# cpu.net
KiCad netlist of a schematic drawn in Altium Designer
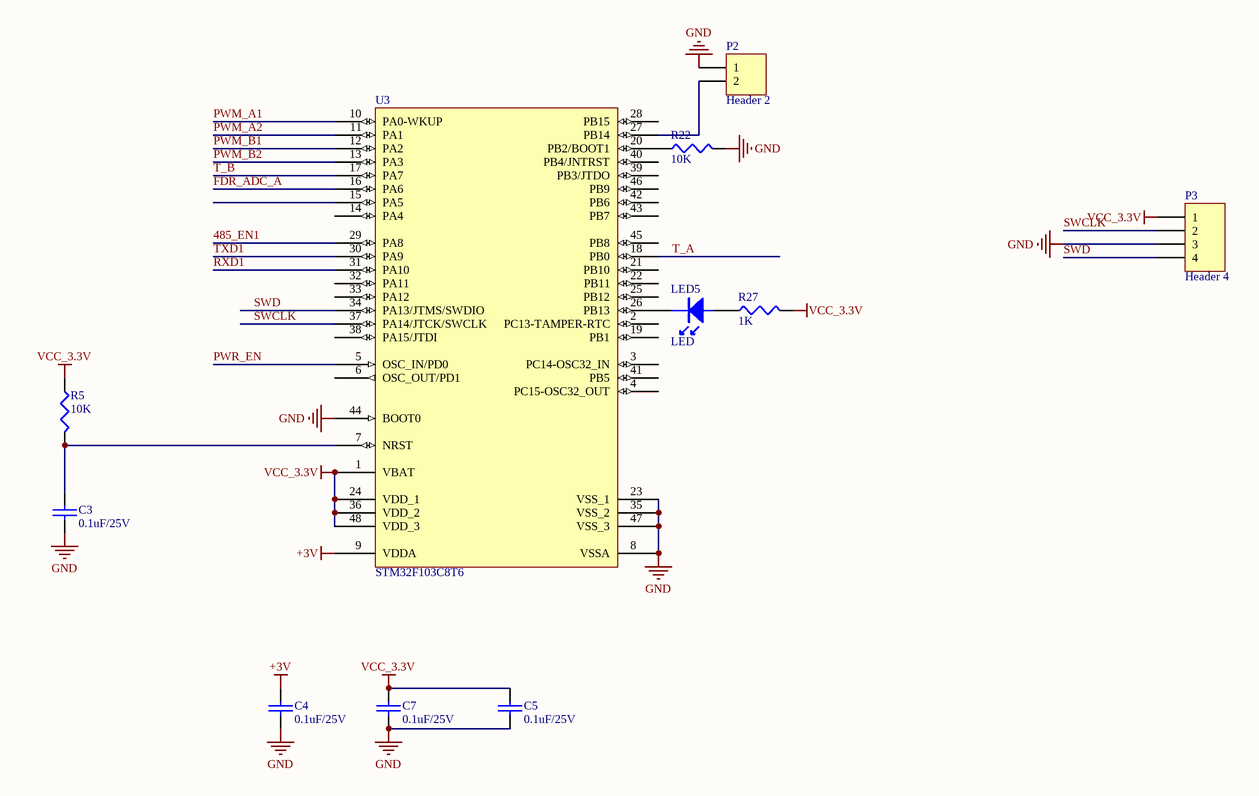
[diagram p0: cpu.SchDoc]

(export (version "E")
  (design (tool "Eeschema 10.0.6"))
  (components
    (comp (ref "C3")
      (value "0.1uF/25V")
      (footprint "0603C")
      (description "Capacitor")
      (libsource (lib "SM") (part "CAP"))
    )
    (comp (ref "C4")
      (value "0.1uF/25V")
      (footprint "0603C")
      (description "Capacitor")
      (libsource (lib "SM") (part "CAP"))
    )
    (comp (ref "C5")
      (value "0.1uF/25V")
      (footprint "0603C")
      (description "Capacitor")
      (libsource (lib "SM") (part "CAP"))
    )
    (comp (ref "C7")
      (value "0.1uF/25V")
      (footprint "0603C")
      (description "Capacitor")
      (libsource (lib "SM") (part "CAP"))
    )
    (comp (ref "LED5") (value "LED") (footprint "0603LED") (libsource (lib "我的元件库") (part "LED")))
    (comp (ref "P2")
      (value "Header 2")
      (footprint "HDR1X2")
      (description "Header, 2-Pin")
      (fields (field (name "PUBLISHER") "Altium Limited"))
      (libsource (lib "Miscellaneous Connectors") (part "Header 2"))
    )
    (comp (ref "P3")
      (value "Header 4")
      (footprint "HDR1X4")
      (description "Header, 4-Pin")
      (fields (field (name "PUBLISHER") "Altium Limited"))
      (libsource (lib "Miscellaneous Connectors") (part "Header 4"))
    )
    (comp (ref "R5")
      (value "10K")
      (footprint "0603R")
      (description "Resistor")
      (fields (field (name "PUBLISHER") "Altium Limited"))
      (libsource (lib "SM") (part "Res3"))
    )
    (comp (ref "R22")
      (value "10K")
      (footprint "0603R")
      (description "Resistor")
      (fields (field (name "PUBLISHER") "Altium Limited"))
      (libsource (lib "SM") (part "Res3"))
    )
    (comp (ref "R27")
      (value "1K")
      (footprint "0603R")
      (libsource (lib "ZWLIntegrated_Library") (part "RES1"))
    )
    (comp (ref "U3")
      (value "STM32F103C8T6")
      (footprint "TQFP-48")
      (description "STM32 ARM-based 32-bit MCU with 64 Kbytes Flash, 48-pin LQFP, Industrial Temperature")
      (fields (field (name "PUBLISHER") "Altium Limited"))
      (libsource (lib "ST Microcontroller 32-Bit STM32") (part "STM32F103C8T6"))
    )
  )
  (nets
    (net (code "1") (name "+3V") (class "Default")
      (node (ref "C4") (pin "2") (pinfunction "2_2") (pintype "passive"))
      (node (ref "U3") (pin "9") (pinfunction "VDDA_9") (pintype "power_in"))
    )
    (net (code "2") (name "/485_EN1") (class "Default")
      (node (ref "U3") (pin "29") (pinfunction "PA8_29") (pintype "bidirectional"))
    )
    (net (code "3") (name "/FDR_ADC_A") (class "Default")
      (node (ref "U3") (pin "16") (pinfunction "PA6_16") (pintype "bidirectional"))
    )
    (net (code "4") (name "/PWM_A1") (class "Default")
      (node (ref "U3") (pin "10") (pinfunction "PA0-WKUP_10") (pintype "bidirectional"))
    )
    (net (code "5") (name "/PWM_A2") (class "Default")
      (node (ref "U3") (pin "11") (pinfunction "PA1_11") (pintype "bidirectional"))
    )
    (net (code "6") (name "/PWM_B1") (class "Default")
      (node (ref "U3") (pin "12") (pinfunction "PA2_12") (pintype "bidirectional"))
    )
    (net (code "7") (name "/PWM_B2") (class "Default")
      (node (ref "U3") (pin "13") (pinfunction "PA3_13") (pintype "bidirectional"))
    )
    (net (code "8") (name "/PWR_EN") (class "Default")
      (node (ref "U3") (pin "5") (pinfunction "OSC_IN/PD0_5") (pintype "input"))
    )
    (net (code "9") (name "/RXD1") (class "Default")
      (node (ref "U3") (pin "31") (pinfunction "PA10_31") (pintype "bidirectional"))
    )
    (net (code "10") (name "/SWCLK") (class "Default")
      (node (ref "P3") (pin "2") (pinfunction "2_2") (pintype "passive"))
      (node (ref "U3") (pin "37") (pinfunction "PA14/JTCK/SWCLK_37") (pintype "bidirectional"))
    )
    (net (code "11") (name "/SWD") (class "Default")
      (node (ref "P3") (pin "4") (pinfunction "4_4") (pintype "passive"))
      (node (ref "U3") (pin "34") (pinfunction "PA13/JTMS/SWDIO_34") (pintype "bidirectional"))
    )
    (net (code "12") (name "/TXD1") (class "Default")
      (node (ref "U3") (pin "30") (pinfunction "PA9_30") (pintype "bidirectional"))
    )
    (net (code "13") (name "/T_A") (class "Default")
      (node (ref "U3") (pin "18") (pinfunction "PB0_18") (pintype "bidirectional"))
    )
    (net (code "14") (name "/T_B") (class "Default")
      (node (ref "U3") (pin "17") (pinfunction "PA7_17") (pintype "bidirectional"))
    )
    (net (code "15") (name "GND") (class "Default")
      (node (ref "C3") (pin "1") (pinfunction "1_1") (pintype "passive"))
      (node (ref "C4") (pin "1") (pinfunction "1_1") (pintype "passive"))
      (node (ref "C5") (pin "1") (pinfunction "1_1") (pintype "passive"))
      (node (ref "C7") (pin "1") (pinfunction "1_1") (pintype "passive"))
      (node (ref "P2") (pin "1") (pinfunction "1_1") (pintype "passive"))
      (node (ref "P3") (pin "3") (pinfunction "3_3") (pintype "passive"))
      (node (ref "R22") (pin "2") (pinfunction "2_2") (pintype "passive"))
      (node (ref "U3") (pin "23") (pinfunction "VSS_1_23") (pintype "power_in"))
      (node (ref "U3") (pin "35") (pinfunction "VSS_2_35") (pintype "power_in"))
      (node (ref "U3") (pin "44") (pinfunction "BOOT0_44") (pintype "input"))
      (node (ref "U3") (pin "47") (pinfunction "VSS_3_47") (pintype "power_in"))
      (node (ref "U3") (pin "8") (pinfunction "VSSA_8") (pintype "power_in"))
    )
    (net (code "16") (name "Net-(LED5-Pad1)") (class "Default")
      (node (ref "LED5") (pin "1") (pinfunction "1_1") (pintype "passive"))
      (node (ref "R27") (pin "1") (pinfunction "1_1") (pintype "passive"))
    )
    (net (code "17") (name "Net-(U3-NRST)") (class "Default")
      (node (ref "C3") (pin "2") (pinfunction "2_2") (pintype "passive"))
      (node (ref "R5") (pin "2") (pinfunction "2_2") (pintype "passive"))
      (node (ref "U3") (pin "7") (pinfunction "NRST_7") (pintype "bidirectional"))
    )
    (net (code "18") (name "Net-(U3-PB2{slash}BOOT1)") (class "Default")
      (node (ref "R22") (pin "1") (pinfunction "1_1") (pintype "passive"))
      (node (ref "U3") (pin "20") (pinfunction "PB2/BOOT1_20") (pintype "bidirectional"))
    )
    (net (code "19") (name "Net-(U3-PB13)") (class "Default")
      (node (ref "LED5") (pin "2") (pinfunction "2_2") (pintype "passive"))
      (node (ref "U3") (pin "26") (pinfunction "PB13_26") (pintype "bidirectional"))
    )
    (net (code "20") (name "Net-(U3-PB14)") (class "Default")
      (node (ref "P2") (pin "2") (pinfunction "2_2") (pintype "passive"))
      (node (ref "U3") (pin "27") (pinfunction "PB14_27") (pintype "bidirectional"))
    )
    (net (code "21") (name "VCC_3.3V") (class "Default")
      (node (ref "C5") (pin "2") (pinfunction "2_2") (pintype "passive"))
      (node (ref "C7") (pin "2") (pinfunction "2_2") (pintype "passive"))
      (node (ref "P3") (pin "1") (pinfunction "1_1") (pintype "passive"))
      (node (ref "R27") (pin "2") (pinfunction "2_2") (pintype "passive"))
      (node (ref "R5") (pin "1") (pinfunction "1_1") (pintype "passive"))
      (node (ref "U3") (pin "1") (pinfunction "VBAT_1") (pintype "power_in"))
      (node (ref "U3") (pin "24") (pinfunction "VDD_1_24") (pintype "power_in"))
      (node (ref "U3") (pin "36") (pinfunction "VDD_2_36") (pintype "power_in"))
      (node (ref "U3") (pin "48") (pinfunction "VDD_3_48") (pintype "power_in"))
    )
    (net (code "22") (name "unconnected-(U3-OSC_OUT{slash}PD1-Pad6)") (class "Default")
      (node (ref "U3") (pin "6") (pinfunction "OSC_OUT/PD1_6") (pintype "output"))
    )
    (net (code "23") (name "unconnected-(U3-PA4-Pad14)") (class "Default")
      (node (ref "U3") (pin "14") (pinfunction "PA4_14") (pintype "bidirectional"))
    )
    (net (code "24") (name "unconnected-(U3-PA5-Pad15)") (class "Default")
      (node (ref "U3") (pin "15") (pinfunction "PA5_15") (pintype "bidirectional"))
    )
    (net (code "25") (name "unconnected-(U3-PA11-Pad32)") (class "Default")
      (node (ref "U3") (pin "32") (pinfunction "PA11_32") (pintype "bidirectional"))
    )
    (net (code "26") (name "unconnected-(U3-PA12-Pad33)") (class "Default")
      (node (ref "U3") (pin "33") (pinfunction "PA12_33") (pintype "bidirectional"))
    )
    (net (code "27") (name "unconnected-(U3-PA15{slash}JTDI-Pad38)") (class "Default")
      (node (ref "U3") (pin "38") (pinfunction "PA15/JTDI_38") (pintype "bidirectional"))
    )
    (net (code "28") (name "unconnected-(U3-PB1-Pad19)") (class "Default")
      (node (ref "U3") (pin "19") (pinfunction "PB1_19") (pintype "bidirectional"))
    )
    (net (code "29") (name "unconnected-(U3-PB3{slash}JTDO-Pad39)") (class "Default")
      (node (ref "U3") (pin "39") (pinfunction "PB3/JTDO_39") (pintype "bidirectional"))
    )
    (net (code "30") (name "unconnected-(U3-PB4{slash}JNTRST-Pad40)") (class "Default")
      (node (ref "U3") (pin "40") (pinfunction "PB4/JNTRST_40") (pintype "bidirectional"))
    )
    (net (code "31") (name "unconnected-(U3-PB5-Pad41)") (class "Default")
      (node (ref "U3") (pin "41") (pinfunction "PB5_41") (pintype "bidirectional"))
    )
    (net (code "32") (name "unconnected-(U3-PB6-Pad42)") (class "Default")
      (node (ref "U3") (pin "42") (pinfunction "PB6_42") (pintype "bidirectional"))
    )
    (net (code "33") (name "unconnected-(U3-PB7-Pad43)") (class "Default")
      (node (ref "U3") (pin "43") (pinfunction "PB7_43") (pintype "bidirectional"))
    )
    (net (code "34") (name "unconnected-(U3-PB8-Pad45)") (class "Default")
      (node (ref "U3") (pin "45") (pinfunction "PB8_45") (pintype "bidirectional"))
    )
    (net (code "35") (name "unconnected-(U3-PB9-Pad46)") (class "Default")
      (node (ref "U3") (pin "46") (pinfunction "PB9_46") (pintype "bidirectional"))
    )
    (net (code "36") (name "unconnected-(U3-PB10-Pad21)") (class "Default")
      (node (ref "U3") (pin "21") (pinfunction "PB10_21") (pintype "bidirectional"))
    )
    (net (code "37") (name "unconnected-(U3-PB11-Pad22)") (class "Default")
      (node (ref "U3") (pin "22") (pinfunction "PB11_22") (pintype "bidirectional"))
    )
    (net (code "38") (name "unconnected-(U3-PB12-Pad25)") (class "Default")
      (node (ref "U3") (pin "25") (pinfunction "PB12_25") (pintype "bidirectional"))
    )
    (net (code "39") (name "unconnected-(U3-PB15-Pad28)") (class "Default")
      (node (ref "U3") (pin "28") (pinfunction "PB15_28") (pintype "bidirectional"))
    )
    (net (code "40") (name "unconnected-(U3-PC13-TAMPER-RTC-Pad2)") (class "Default")
      (node (ref "U3") (pin "2") (pinfunction "PC13-TAMPER-RTC_2") (pintype "bidirectional"))
    )
    (net (code "41") (name "unconnected-(U3-PC14-OSC32_IN-Pad3)") (class "Default")
      (node (ref "U3") (pin "3") (pinfunction "PC14-OSC32_IN_3") (pintype "bidirectional"))
    )
    (net (code "42") (name "unconnected-(U3-PC15-OSC32_OUT-Pad4)") (class "Default")
      (node (ref "U3") (pin "4") (pinfunction "PC15-OSC32_OUT_4") (pintype "bidirectional"))
    )
  )
)
